# DC_Step-Down_Converter.net
KiCad netlist of a schematic drawn in Altium Designer
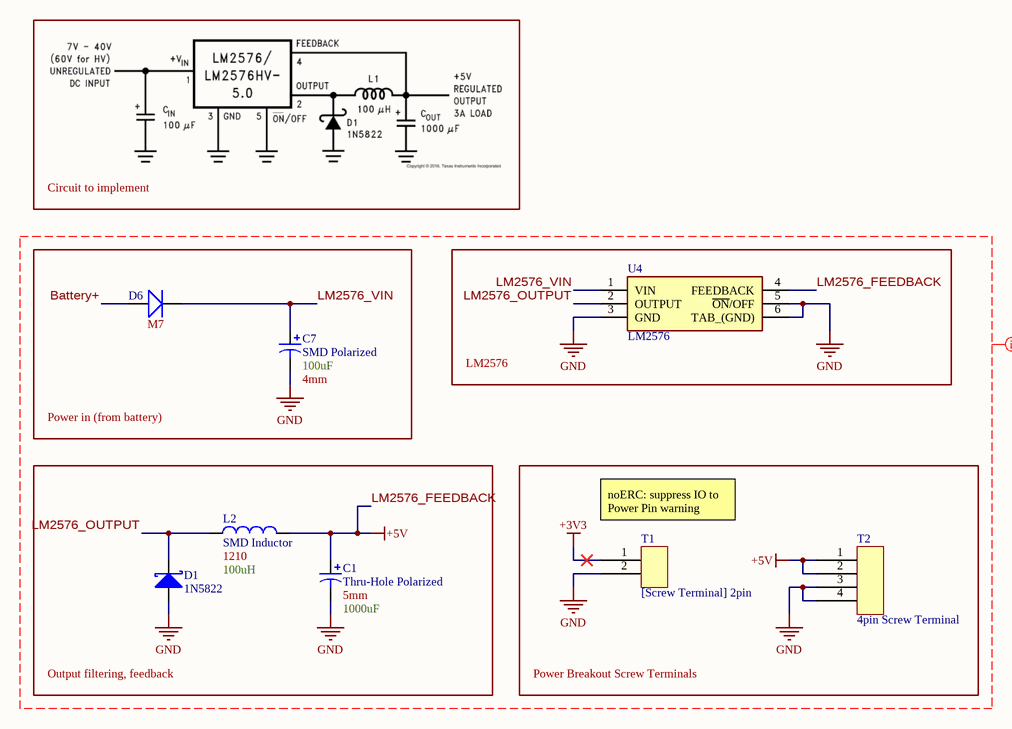
[diagram p0: DC Step-Down Converter.SchDoc]

(export (version "E")
  (design (tool "Eeschema 10.0.6"))
  (components
    (comp (ref "C1")
      (value "Thru-Hole Polarized")
      (footprint "[Cap] Thru-Hole Polarized 5mm")
      (fields (field (name "PIN SPACING") "5mm") (field (name "CAPACITANCE") "1000uF"))
      (libsource (lib "RADM Components") (part "[Cap] Thru-Hole Polarized"))
    )
    (comp (ref "C7")
      (value "SMD Polarized")
      (footprint "[Cap] SMD Polarized, 4mm")
      (fields (field (name "CAPACITANCE") "100uF") (field (name "DIAMETER") "4mm"))
      (libsource (lib "RADM Components") (part "[Cap] SMD Polarized"))
    )
    (comp (ref "D1")
      (value "1N5822")
      (footprint "[Diode] Thru-Hole Schottky")
      (fields (field (name "MOUSER PART #") "511-1N5822"))
      (libsource (lib "RADM Components") (part "[Diode] Thru-Hole Schottky"))
    )
    (comp (ref "D6")
      (value "Rectifier")
      (footprint "[Diode] SMD M7")
      (description "Generic")
      (fields (field (name "SIZE PACKAGE") "M7"))
      (libsource (lib "RADM Components") (part "[Diode] SMD Rectifier"))
    )
    (comp (ref "L2")
      (value "SMD Inductor")
      (footprint "[Inductor] SMD 1210")
      (fields (field (name "SIZE PACKAGE") "1210") (field (name "INDUCTANCE") "100uH"))
      (libsource (lib "RADM Components") (part "[Inductor] SMD Inductor"))
    )
    (comp (ref "T1")
      (value "[Screw Terminal] 2pin")
      (footprint "[Screw Terminal] 2pin")
      (libsource (lib "RADM Components") (part "[Screw Terminal] 2pin"))
    )
    (comp (ref "T2")
      (value "4pin Screw Terminal")
      (footprint "[Screw Terminal] 4pin")
      (libsource (lib "RADM Components") (part "[Screw Terminal] 4pin"))
    )
    (comp (ref "U4")
      (value "LM2576")
      (footprint "[IC] Buck Converter")
      (libsource (lib "RADM Components") (part "[IC] Buck Converter"))
    )
  )
  (nets
    (net (code "1") (name "+3V3") (class "Default") (node (ref "T1") (pin "1") (pintype "power_in")))
    (net (code "2") (name "+5V") (class "Default")
      (node (ref "C1") (pin "1") (pinfunction "1_1") (pintype "passive"))
      (node (ref "L2") (pin "2") (pinfunction "2_2") (pintype "passive"))
      (node (ref "T2") (pin "1") (pintype "power_in"))
      (node (ref "T2") (pin "2") (pintype "power_in"))
      (node (ref "U4") (pin "4") (pinfunction "FEEDBACK_4") (pintype "power_in"))
    )
    (net (code "3") (name "/Battery+") (class "Default")
      (node (ref "D6") (pin "2") (pinfunction "Anode_2") (pintype "power_in"))
    )
    (net (code "4") (name "/LM2576_OUTPUT") (class "Default")
      (node (ref "D1") (pin "1") (pinfunction "K_1") (pintype "passive"))
      (node (ref "L2") (pin "1") (pinfunction "1_1") (pintype "passive"))
      (node (ref "U4") (pin "2") (pinfunction "OUTPUT_2") (pintype "power_in"))
    )
    (net (code "5") (name "/LM2576_VIN") (class "Default")
      (node (ref "C7") (pin "1") (pinfunction "1_1") (pintype "passive"))
      (node (ref "D6") (pin "1") (pinfunction "Cathode_1") (pintype "power_in"))
      (node (ref "U4") (pin "1") (pinfunction "VIN_1") (pintype "power_in"))
    )
    (net (code "6") (name "GND") (class "Default")
      (node (ref "C1") (pin "2") (pinfunction "2_2") (pintype "passive"))
      (node (ref "C7") (pin "2") (pinfunction "2_2") (pintype "passive"))
      (node (ref "D1") (pin "2") (pinfunction "A_2") (pintype "passive"))
      (node (ref "T1") (pin "2") (pintype "power_in"))
      (node (ref "T2") (pin "3") (pintype "power_in"))
      (node (ref "T2") (pin "4") (pintype "power_in"))
      (node (ref "U4") (pin "3") (pinfunction "GND_3") (pintype "power_in"))
      (node (ref "U4") (pin "5") (pinfunction "~{ON}/OFF_5") (pintype "power_in"))
      (node (ref "U4") (pin "6") (pinfunction "TAB_(GND)_6") (pintype "power_in"))
    )
  )
)
